# Page06_CPU_IO.net
KiCad netlist of a schematic drawn in Altium Designer
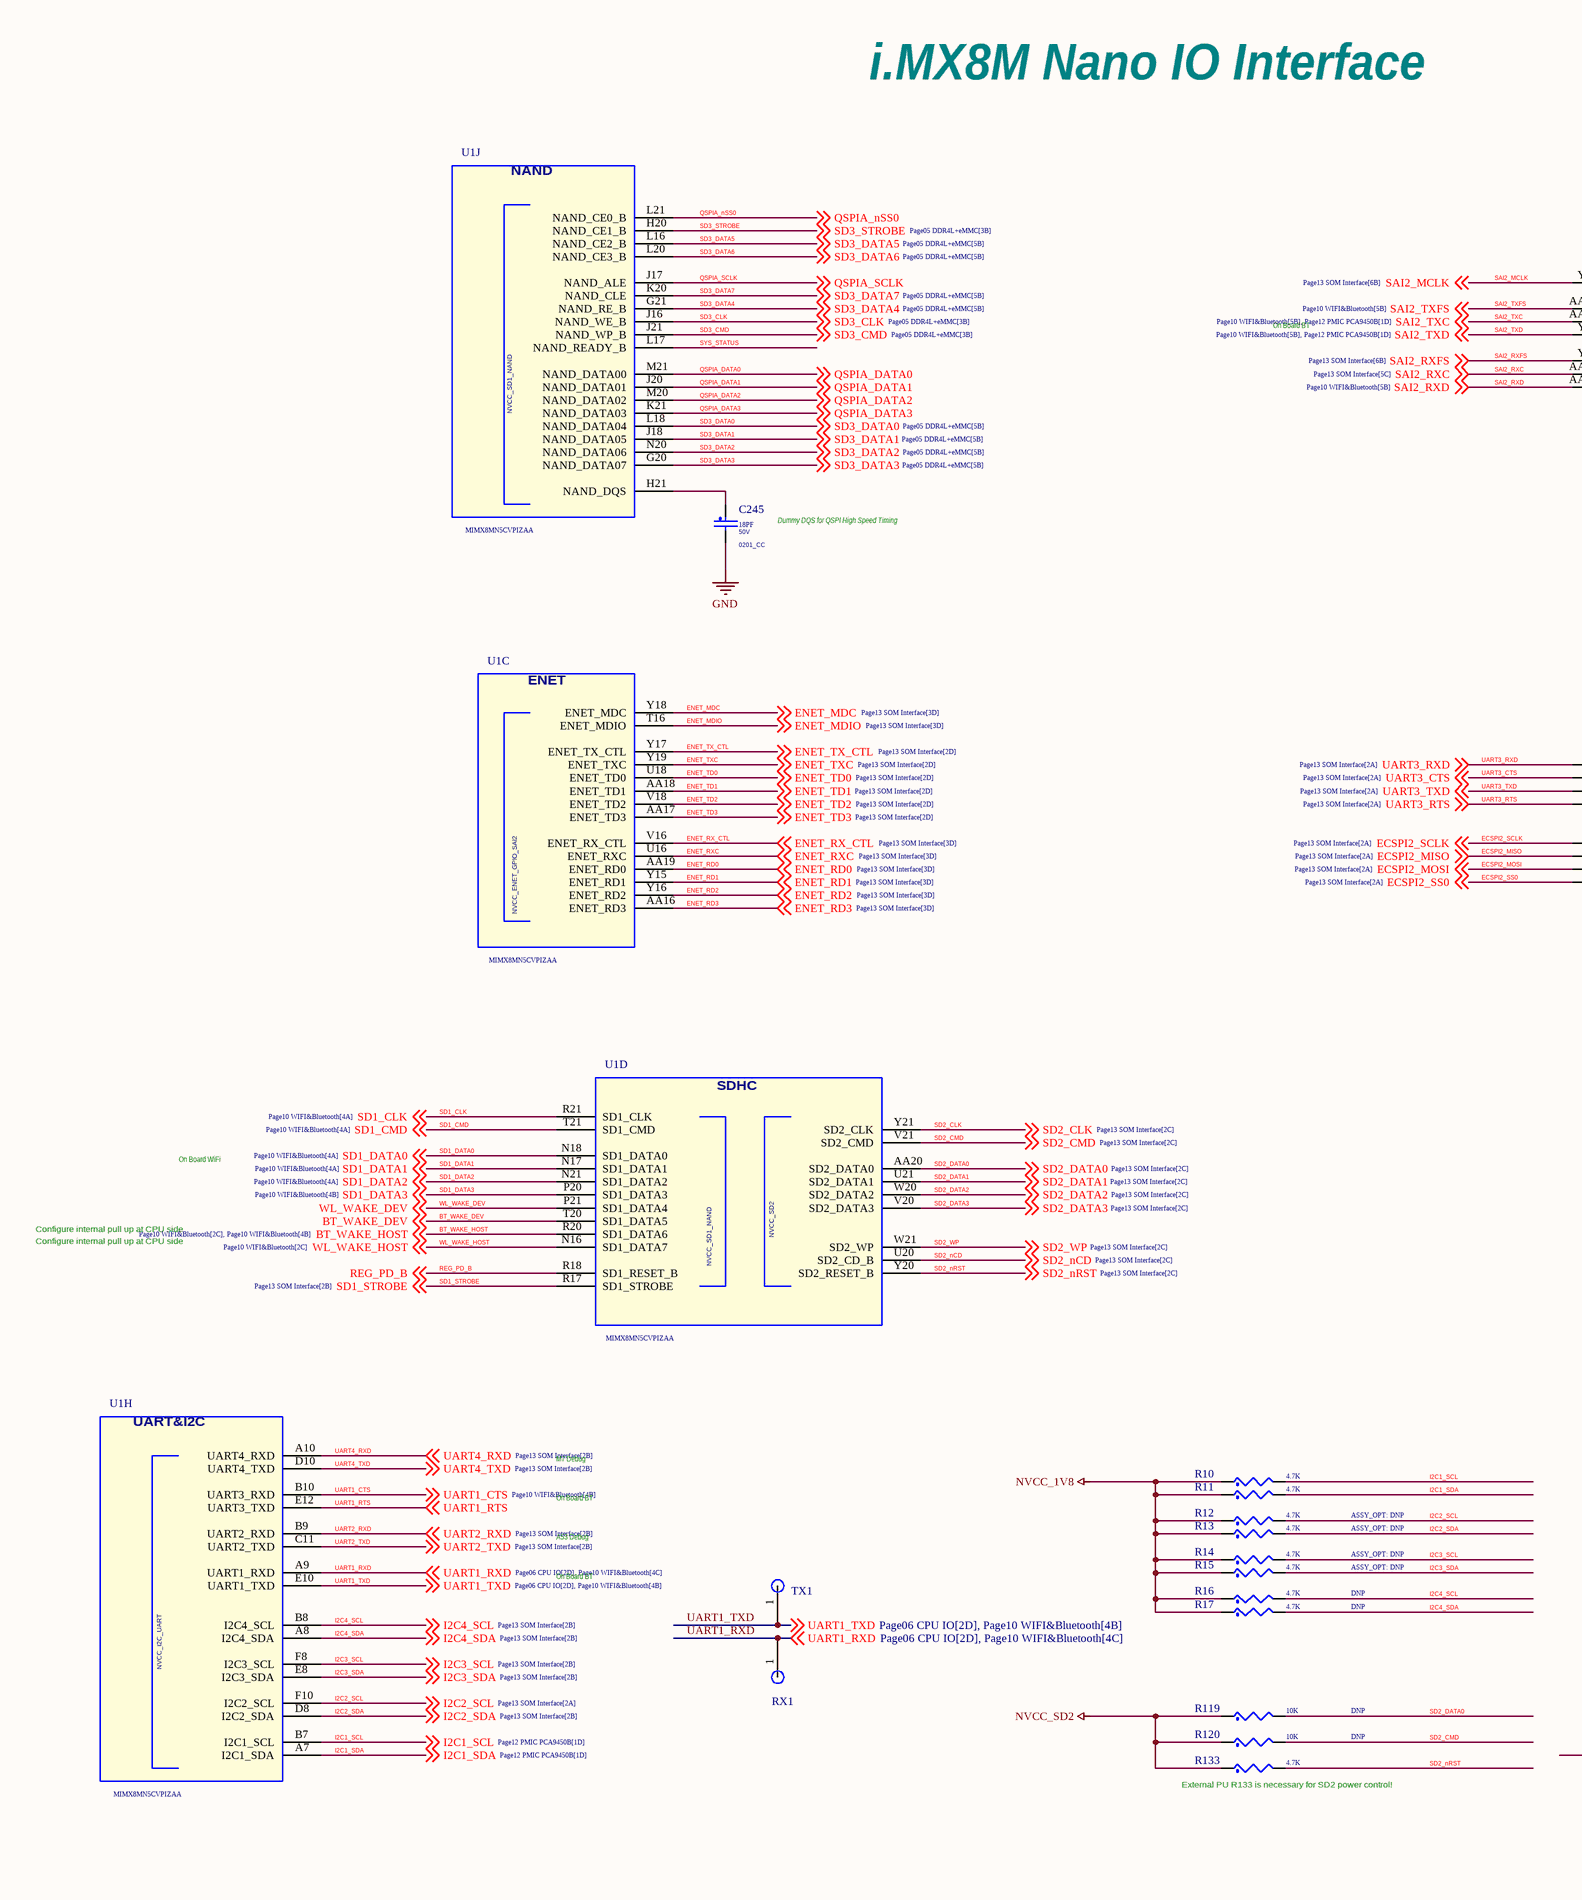
[diagram p0: Page06 CPU IO.SchDoc, left]
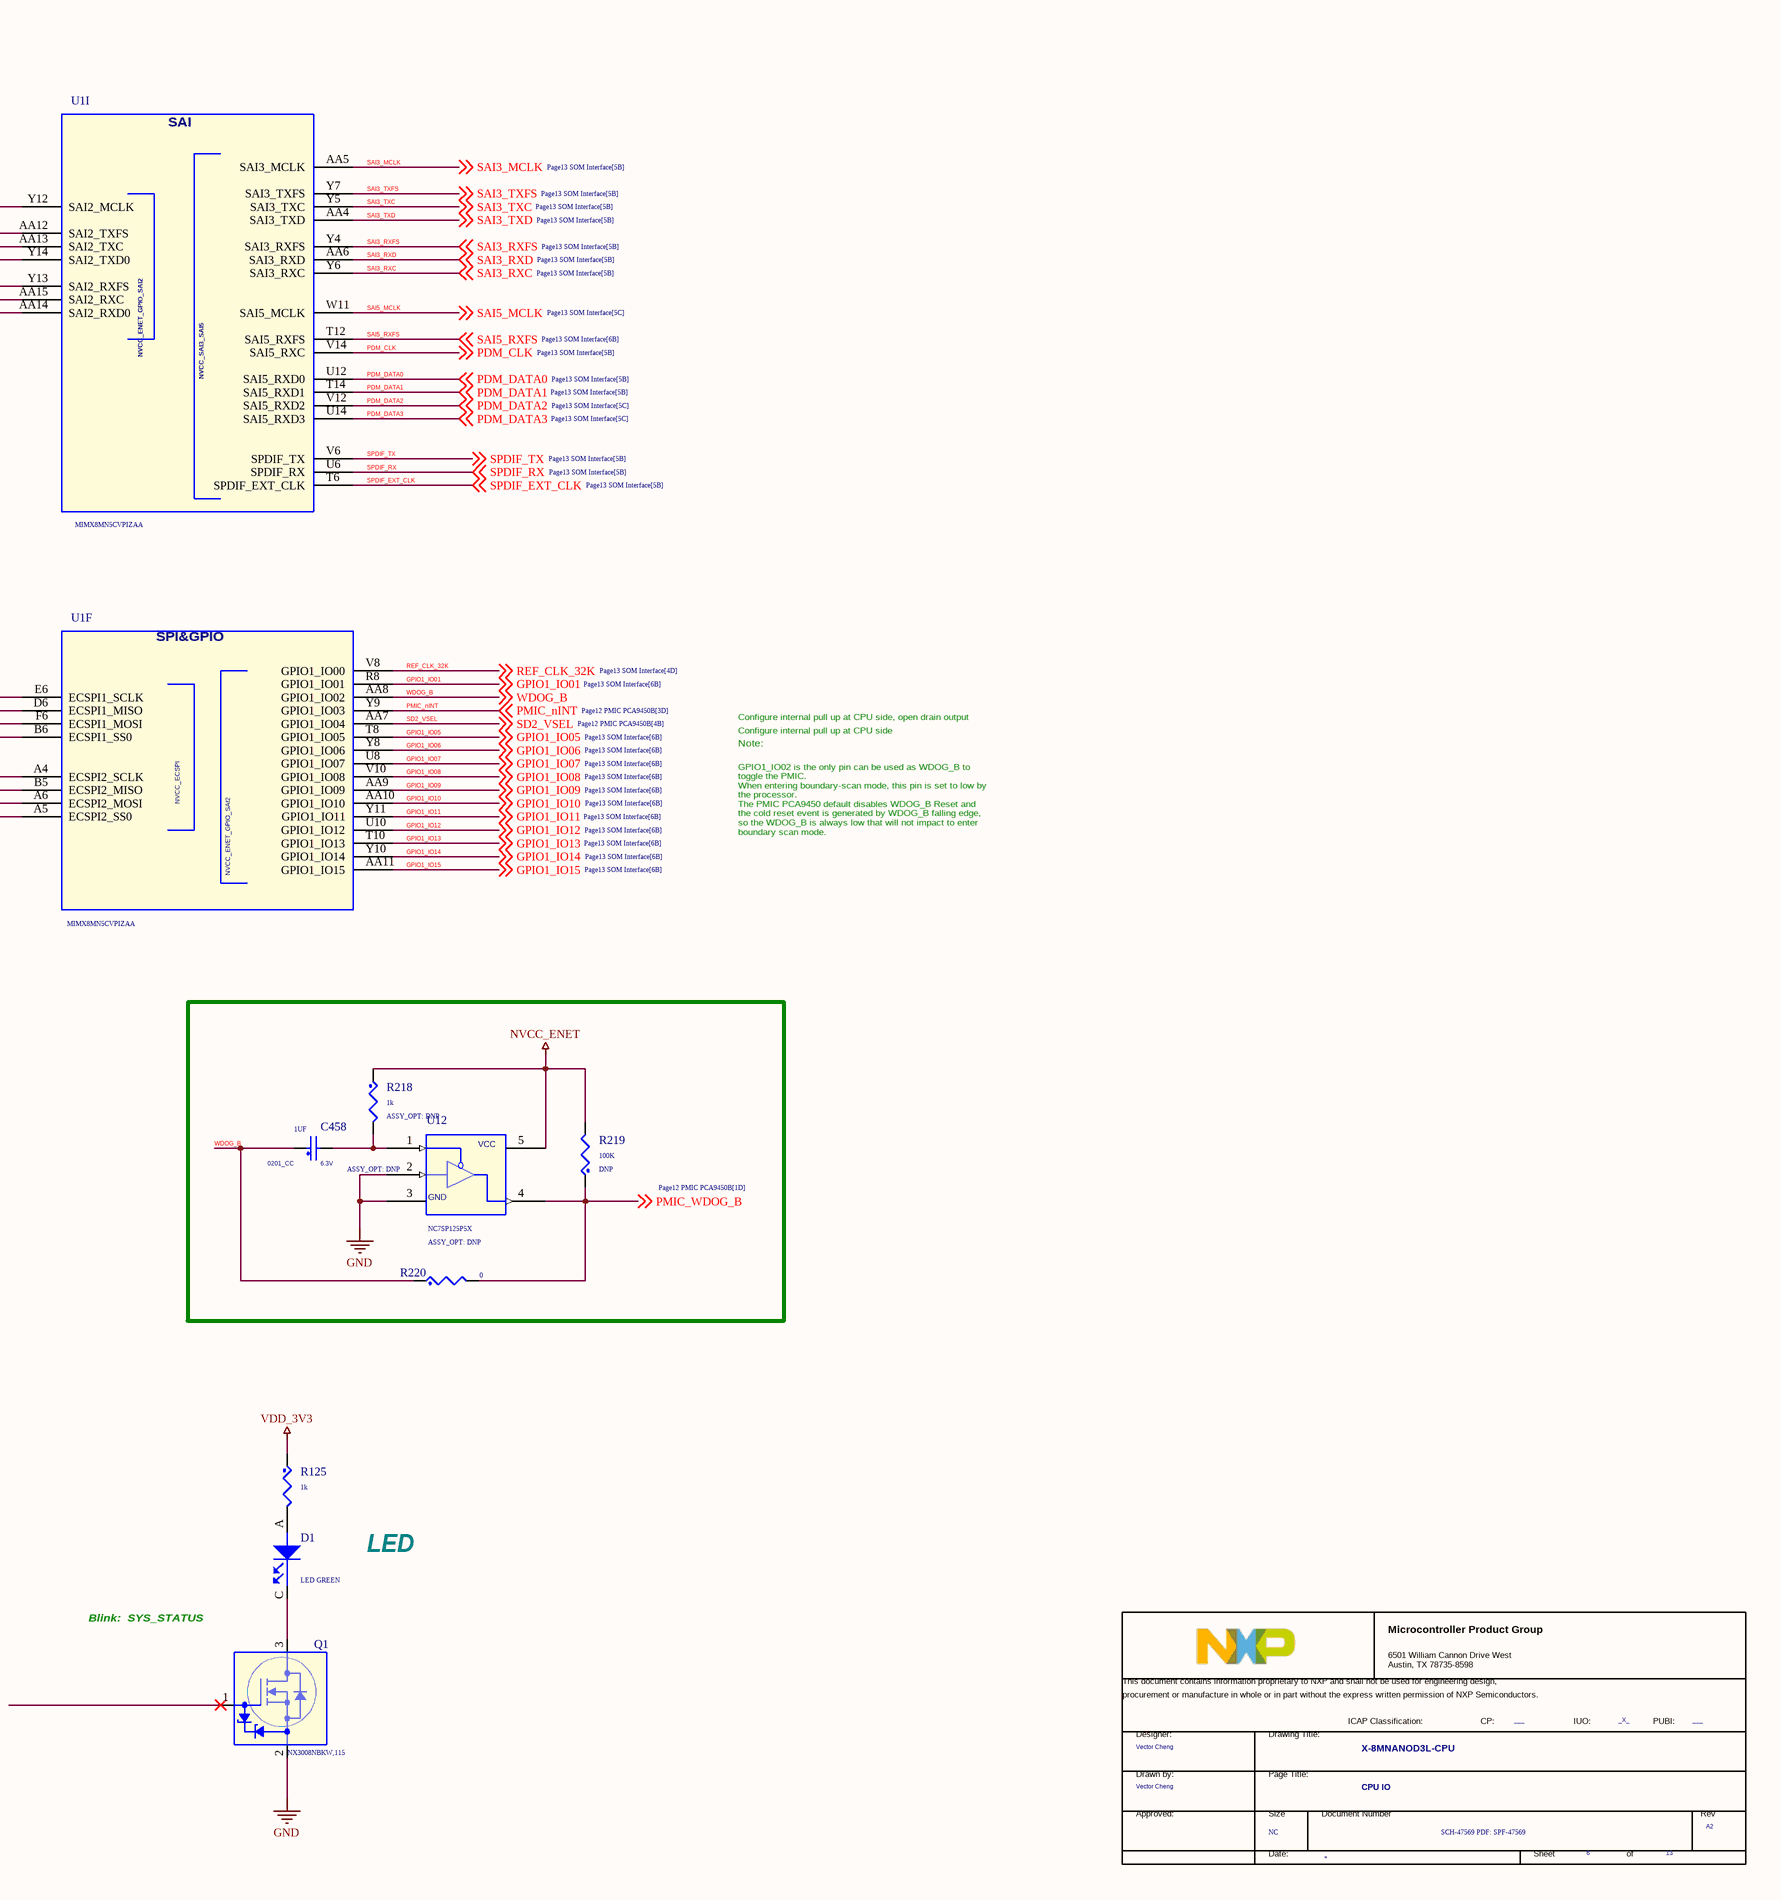
[diagram p1: Page06 CPU IO.SchDoc, right]

(export (version "E")
  (design (tool "Eeschema 10.0.6"))
  (components
    (comp (ref "C245")
      (value "18PF")
      (footprint "0201_CC - C")
      (description "CAP CER 18pF 50V 5% C0G 0201")
      (fields
        (field (name "VOLTAGE") "50V")
        (field (name "TOLERANCE") "5%")
        (field (name "PCB FOOTPRINT") "0201_CC")
      )
      (libsource (lib "*") (part "CAP_NP"))
    )
    (comp (ref "C458")
      (value "1UF")
      (footprint "0201_CC - C")
      (description "CAP CER 1uF 6.3V 20% X5R 0201")
      (fields
        (field (name "ASSY_OPT") "DNP")
        (field (name "PCB FOOTPRINT") "0201_CC")
        (field (name "TOLERANCE") "20%")
        (field (name "VOLTAGE") "6.3V")
      )
      (libsource (lib "*") (part "CAP_NP"))
    )
    (comp (ref "D1")
      (value "LED GREEN")
      (footprint "LED_0603")
      (description "LED GRN SGL 25MA SMT 0603")
      (fields (field (name "VOLTAGE") "2V"))
      (libsource (lib "*") (part "LED"))
    )
    (comp (ref "Q1")
      (value "NX3008NBKW,115")
      (footprint "sc70_3")
      (description "TRAN NMOS SW 30V 350mA AEC-Q101 SC-70")
      (libsource (lib "*") (part "NMOS_NX3008NBK"))
    )
    (comp (ref "R10")
      (value "4.7K")
      (footprint "0201_RES")
      (description "RES MF 4.7K 1/20W 5% AEC-Q200 0201")
      (fields (field (name "TOLERANCE") "5%"))
      (libsource (lib "*") (part "RES"))
    )
    (comp (ref "R11")
      (value "4.7K")
      (footprint "0201_RES")
      (description "RES MF 4.7K 1/20W 5% AEC-Q200 0201")
      (fields (field (name "TOLERANCE") "5%"))
      (libsource (lib "*") (part "RES"))
    )
    (comp (ref "R12")
      (value "4.7K")
      (footprint "0201_RES")
      (description "RES MF 4.7K 1/20W 5% AEC-Q200 0201")
      (fields (field (name "ASSY_OPT") "DNP") (field (name "TOLERANCE") "5%"))
      (libsource (lib "*") (part "RES"))
    )
    (comp (ref "R13")
      (value "4.7K")
      (footprint "0201_RES")
      (description "RES MF 4.7K 1/20W 5% AEC-Q200 0201")
      (fields (field (name "ASSY_OPT") "DNP") (field (name "TOLERANCE") "5%"))
      (libsource (lib "*") (part "RES"))
    )
    (comp (ref "R14")
      (value "4.7K")
      (footprint "0201_RES")
      (description "RES MF 4.7K 1/20W 5% AEC-Q200 0201")
      (fields (field (name "ASSY_OPT") "DNP") (field (name "TOLERANCE") "5%"))
      (libsource (lib "*") (part "RES"))
    )
    (comp (ref "R15")
      (value "4.7K")
      (footprint "0201_RES")
      (description "RES MF 4.7K 1/20W 5% AEC-Q200 0201")
      (fields (field (name "ASSY_OPT") "DNP") (field (name "TOLERANCE") "5%"))
      (libsource (lib "*") (part "RES"))
    )
    (comp (ref "R16")
      (value "4.7K")
      (footprint "0201_RES")
      (description "RES MF 4.7K 1/20W 5% AEC-Q200 0201")
      (fields (field (name "ASSY_OPT") "DNP") (field (name "TOLERANCE") "5%"))
      (libsource (lib "*") (part "RES"))
    )
    (comp (ref "R17")
      (value "4.7K")
      (footprint "0201_RES")
      (description "RES MF 4.7K 1/20W 5% AEC-Q200 0201")
      (fields (field (name "ASSY_OPT") "DNP") (field (name "TOLERANCE") "5%"))
      (libsource (lib "*") (part "RES"))
    )
    (comp (ref "R119")
      (value "10K")
      (footprint "0201_RES")
      (description "RES MF 10K 1/20W 5% 0201")
      (fields (field (name "ASSY_OPT") "DNP") (field (name "TOLERANCE") "5%"))
      (libsource (lib "*") (part "RES"))
    )
    (comp (ref "R120")
      (value "10K")
      (footprint "0201_RES")
      (description "RES MF 10K 1/20W 5% 0201")
      (fields (field (name "ASSY_OPT") "DNP") (field (name "TOLERANCE") "5%"))
      (libsource (lib "*") (part "RES"))
    )
    (comp (ref "R125")
      (value "1k")
      (footprint "0201_RES")
      (description "RES MF 1.0K OHM 1/20W 1% 30V -55+155C 0201")
      (fields (field (name "VOLTAGE") "30") (field (name "TOLERANCE") "1%"))
      (libsource (lib "*") (part "RES"))
    )
    (comp (ref "R133")
      (value "4.7K")
      (footprint "0201_RES")
      (description "RES MF 4.7K 1/20W 5% AEC-Q200 0201")
      (fields (field (name "TOLERANCE") "5%"))
      (libsource (lib "*") (part "RES"))
    )
    (comp (ref "R218")
      (value "1k")
      (footprint "0201_RES")
      (description "RES MF 1.0K OHM 1/20W 1% 30V -55+155C 0201")
      (fields (field (name "ASSY_OPT") "DNP") (field (name "TOLERANCE") "1%") (field (name "VOLTAGE") "30"))
      (libsource (lib "*") (part "RES"))
    )
    (comp (ref "R219")
      (value "100K")
      (footprint "0201_RES")
      (description "RES MF 100K 1/20W 1% 0201")
      (fields (field (name "ASSY_OPT") "DNP") (field (name "TOLERANCE") "1%"))
      (libsource (lib "*") (part "RES"))
    )
    (comp (ref "R220")
      (value "0")
      (footprint "0402_CC")
      (description "RES MF ZERO OHM 1/16W 5% 0402")
      (fields (field (name "TOLERANCE") "5%") (field (name "VOLTAGE") "1/16W"))
      (libsource (lib "*") (part "RES"))
    )
    (comp (ref "RX1")
      (value "Test Pin1")
      (footprint "Test Pin")
      (libsource (lib "Altium starter project NANO") (part "Test Pin1"))
    )
    (comp (ref "TX1")
      (value "Test Pin1")
      (footprint "Test Pin")
      (libsource (lib "Altium starter project NANO") (part "Test Pin1"))
    )
    (comp (ref "U1")
      (value "MIMX8MN5CVPIZAA")
      (footprint "BGA306C50P21X21_1100X1100X101")
      (description "IC CPU QUAD CORTEX A53+M7 1.4GHZ -- BGA306")
      (libsource (lib "*") (part "MIMX8MN"))
    )
    (comp (ref "U12")
      (value "NC7SP125P5X")
      (footprint "SC70-5_A")
      (description "IC BUF TS 0.9-3.6V")
      (fields (field (name "ASSY_OPT") "DNP"))
      (libsource (lib "*") (part "1G125"))
    )
  )
  (nets
    (net (code "1") (name "/SYS_STATUS") (class "Default")
      (node (ref "U1") (pin "L17") (pinfunction "NAND_READY_B_L17") (pintype "passive"))
    )
    (net (code "2") (name "BT_WAKE_DEV") (class "Default")
      (node (ref "U1") (pin "T20") (pinfunction "SD1_DATA5_T20") (pintype "passive"))
    )
    (net (code "3") (name "BT_WAKE_HOST") (class "Default")
      (node (ref "U1") (pin "R20") (pinfunction "SD1_DATA6_R20") (pintype "passive"))
    )
    (net (code "4") (name "ECSPI2_MISO") (class "Default")
      (node (ref "U1") (pin "B5") (pinfunction "ECSPI2_MISO_B5") (pintype "passive"))
    )
    (net (code "5") (name "ECSPI2_MOSI") (class "Default")
      (node (ref "U1") (pin "A6") (pinfunction "ECSPI2_MOSI_A6") (pintype "passive"))
    )
    (net (code "6") (name "ECSPI2_SCLK") (class "Default")
      (node (ref "U1") (pin "A4") (pinfunction "ECSPI2_SCLK_A4") (pintype "passive"))
    )
    (net (code "7") (name "ECSPI2_SS0") (class "Default")
      (node (ref "U1") (pin "A5") (pinfunction "ECSPI2_SS0_A5") (pintype "passive"))
    )
    (net (code "8") (name "ENET_MDC") (class "Default")
      (node (ref "U1") (pin "Y18") (pinfunction "ENET_MDC_Y18") (pintype "passive"))
    )
    (net (code "9") (name "ENET_MDIO") (class "Default")
      (node (ref "U1") (pin "T16") (pinfunction "ENET_MDIO_T16") (pintype "passive"))
    )
    (net (code "10") (name "ENET_RD0") (class "Default")
      (node (ref "U1") (pin "AA19") (pinfunction "ENET_RD0_AA19") (pintype "passive"))
    )
    (net (code "11") (name "ENET_RD1") (class "Default")
      (node (ref "U1") (pin "Y15") (pinfunction "ENET_RD1_Y15") (pintype "passive"))
    )
    (net (code "12") (name "ENET_RD2") (class "Default")
      (node (ref "U1") (pin "Y16") (pinfunction "ENET_RD2_Y16") (pintype "passive"))
    )
    (net (code "13") (name "ENET_RD3") (class "Default")
      (node (ref "U1") (pin "AA16") (pinfunction "ENET_RD3_AA16") (pintype "passive"))
    )
    (net (code "14") (name "ENET_RXC") (class "Default")
      (node (ref "U1") (pin "U16") (pinfunction "ENET_RXC_U16") (pintype "passive"))
    )
    (net (code "15") (name "ENET_RX_CTL") (class "Default")
      (node (ref "U1") (pin "V16") (pinfunction "ENET_RX_CTL_V16") (pintype "passive"))
    )
    (net (code "16") (name "ENET_TD0") (class "Default")
      (node (ref "U1") (pin "U18") (pinfunction "ENET_TD0_U18") (pintype "passive"))
    )
    (net (code "17") (name "ENET_TD1") (class "Default")
      (node (ref "U1") (pin "AA18") (pinfunction "ENET_TD1_AA18") (pintype "passive"))
    )
    (net (code "18") (name "ENET_TD2") (class "Default")
      (node (ref "U1") (pin "V18") (pinfunction "ENET_TD2_V18") (pintype "passive"))
    )
    (net (code "19") (name "ENET_TD3") (class "Default")
      (node (ref "U1") (pin "AA17") (pinfunction "ENET_TD3_AA17") (pintype "passive"))
    )
    (net (code "20") (name "ENET_TXC") (class "Default")
      (node (ref "U1") (pin "Y19") (pinfunction "ENET_TXC_Y19") (pintype "passive"))
    )
    (net (code "21") (name "ENET_TX_CTL") (class "Default")
      (node (ref "U1") (pin "Y17") (pinfunction "ENET_TX_CTL_Y17") (pintype "passive"))
    )
    (net (code "22") (name "GND") (class "Default")
      (node (ref "C245") (pin "2") (pinfunction "2_2") (pintype "passive"))
      (node (ref "Q1") (pin "2") (pinfunction "SOURCE_2") (pintype "passive"))
      (node (ref "U12") (pin "2") (pinfunction "A_2") (pintype "input"))
      (node (ref "U12") (pin "3") (pinfunction "GND_3") (pintype "power_in"))
    )
    (net (code "23") (name "GPIO1_IO01") (class "Default")
      (node (ref "U1") (pin "R8") (pinfunction "GPIO1_IO01_R8") (pintype "passive"))
    )
    (net (code "24") (name "GPIO1_IO05") (class "Default")
      (node (ref "U1") (pin "T8") (pinfunction "GPIO1_IO05_T8") (pintype "passive"))
    )
    (net (code "25") (name "GPIO1_IO06") (class "Default")
      (node (ref "U1") (pin "Y8") (pinfunction "GPIO1_IO06_Y8") (pintype "passive"))
    )
    (net (code "26") (name "GPIO1_IO07") (class "Default")
      (node (ref "U1") (pin "U8") (pinfunction "GPIO1_IO07_U8") (pintype "passive"))
    )
    (net (code "27") (name "GPIO1_IO08") (class "Default")
      (node (ref "U1") (pin "V10") (pinfunction "GPIO1_IO08_V10") (pintype "passive"))
    )
    (net (code "28") (name "GPIO1_IO09") (class "Default")
      (node (ref "U1") (pin "AA9") (pinfunction "GPIO1_IO09_AA9") (pintype "passive"))
    )
    (net (code "29") (name "GPIO1_IO10") (class "Default")
      (node (ref "U1") (pin "AA10") (pinfunction "GPIO1_IO10_AA10") (pintype "passive"))
    )
    (net (code "30") (name "GPIO1_IO11") (class "Default")
      (node (ref "U1") (pin "Y11") (pinfunction "GPIO1_IO11_Y11") (pintype "passive"))
    )
    (net (code "31") (name "GPIO1_IO12") (class "Default")
      (node (ref "U1") (pin "U10") (pinfunction "GPIO1_IO12_U10") (pintype "passive"))
    )
    (net (code "32") (name "GPIO1_IO13") (class "Default")
      (node (ref "U1") (pin "T10") (pinfunction "GPIO1_IO13_T10") (pintype "passive"))
    )
    (net (code "33") (name "GPIO1_IO14") (class "Default")
      (node (ref "U1") (pin "Y10") (pinfunction "GPIO1_IO14_Y10") (pintype "passive"))
    )
    (net (code "34") (name "GPIO1_IO15") (class "Default")
      (node (ref "U1") (pin "AA11") (pinfunction "GPIO1_IO15_AA11") (pintype "passive"))
    )
    (net (code "35") (name "I2C1_SCL") (class "Default")
      (node (ref "R10") (pin "2") (pinfunction "2_2") (pintype "passive"))
      (node (ref "U1") (pin "B7") (pinfunction "I2C1_SCL_B7") (pintype "passive"))
    )
    (net (code "36") (name "I2C1_SDA") (class "Default")
      (node (ref "R11") (pin "2") (pinfunction "2_2") (pintype "passive"))
      (node (ref "U1") (pin "A7") (pinfunction "I2C1_SDA_A7") (pintype "passive"))
    )
    (net (code "37") (name "I2C2_SCL") (class "Default")
      (node (ref "R12") (pin "2") (pinfunction "2_2") (pintype "passive"))
      (node (ref "U1") (pin "F10") (pinfunction "I2C2_SCL_F10") (pintype "passive"))
    )
    (net (code "38") (name "I2C2_SDA") (class "Default")
      (node (ref "R13") (pin "2") (pinfunction "2_2") (pintype "passive"))
      (node (ref "U1") (pin "D8") (pinfunction "I2C2_SDA_D8") (pintype "passive"))
    )
    (net (code "39") (name "I2C3_SCL") (class "Default")
      (node (ref "R14") (pin "2") (pinfunction "2_2") (pintype "passive"))
      (node (ref "U1") (pin "F8") (pinfunction "I2C3_SCL_F8") (pintype "passive"))
    )
    (net (code "40") (name "I2C3_SDA") (class "Default")
      (node (ref "R15") (pin "2") (pinfunction "2_2") (pintype "passive"))
      (node (ref "U1") (pin "E8") (pinfunction "I2C3_SDA_E8") (pintype "passive"))
    )
    (net (code "41") (name "I2C4_SCL") (class "Default")
      (node (ref "R16") (pin "2") (pinfunction "2_2") (pintype "passive"))
      (node (ref "U1") (pin "B8") (pinfunction "I2C4_SCL_B8") (pintype "passive"))
    )
    (net (code "42") (name "I2C4_SDA") (class "Default")
      (node (ref "R17") (pin "2") (pinfunction "2_2") (pintype "passive"))
      (node (ref "U1") (pin "A8") (pinfunction "I2C4_SDA_A8") (pintype "passive"))
    )
    (net (code "43") (name "NVCC_1V8") (class "Default")
      (node (ref "R10") (pin "1") (pinfunction "1_1") (pintype "passive"))
      (node (ref "R11") (pin "1") (pinfunction "1_1") (pintype "passive"))
      (node (ref "R12") (pin "1") (pinfunction "1_1") (pintype "passive"))
      (node (ref "R13") (pin "1") (pinfunction "1_1") (pintype "passive"))
      (node (ref "R14") (pin "1") (pinfunction "1_1") (pintype "passive"))
      (node (ref "R15") (pin "1") (pinfunction "1_1") (pintype "passive"))
      (node (ref "R16") (pin "1") (pinfunction "1_1") (pintype "passive"))
      (node (ref "R17") (pin "1") (pinfunction "1_1") (pintype "passive"))
    )
    (net (code "44") (name "NVCC_ENET") (class "Default")
      (node (ref "R218") (pin "1") (pinfunction "1_1") (pintype "passive"))
      (node (ref "R219") (pin "2") (pinfunction "2_2") (pintype "passive"))
      (node (ref "U12") (pin "5") (pinfunction "VCC_5") (pintype "power_in"))
    )
    (net (code "45") (name "NVCC_SD2") (class "Default")
      (node (ref "R119") (pin "1") (pinfunction "1_1") (pintype "passive"))
      (node (ref "R120") (pin "1") (pinfunction "1_1") (pintype "passive"))
      (node (ref "R133") (pin "1") (pinfunction "1_1") (pintype "passive"))
    )
    (net (code "46") (name "Net-(D1-ANODE)") (class "Default")
      (node (ref "D1") (pin "A") (pinfunction "ANODE_A") (pintype "passive"))
      (node (ref "R125") (pin "2") (pinfunction "2_2") (pintype "passive"))
    )
    (net (code "47") (name "Net-(D1-CATHODE)") (class "Default")
      (node (ref "D1") (pin "C") (pinfunction "CATHODE_C") (pintype "passive"))
      (node (ref "Q1") (pin "3") (pinfunction "DRAIN_3") (pintype "passive"))
    )
    (net (code "48") (name "Net-(U1J-NAND_DQS)") (class "Default")
      (node (ref "C245") (pin "1") (pinfunction "1_1") (pintype "passive"))
      (node (ref "U1") (pin "H21") (pinfunction "NAND_DQS_H21") (pintype "passive"))
    )
    (net (code "49") (name "Net-(U12-~{OE})") (class "Default")
      (node (ref "C458") (pin "2") (pinfunction "2_2") (pintype "passive"))
      (node (ref "R218") (pin "2") (pinfunction "2_2") (pintype "passive"))
      (node (ref "U12") (pin "1") (pinfunction "~{OE}_1") (pintype "input"))
    )
    (net (code "50") (name "PDM_CLK") (class "Default")
      (node (ref "U1") (pin "V14") (pinfunction "SAI5_RXC_V14") (pintype "passive"))
    )
    (net (code "51") (name "PDM_DATA0") (class "Default")
      (node (ref "U1") (pin "U12") (pinfunction "SAI5_RXD0_U12") (pintype "passive"))
    )
    (net (code "52") (name "PDM_DATA1") (class "Default")
      (node (ref "U1") (pin "T14") (pinfunction "SAI5_RXD1_T14") (pintype "passive"))
    )
    (net (code "53") (name "PDM_DATA2") (class "Default")
      (node (ref "U1") (pin "V12") (pinfunction "SAI5_RXD2_V12") (pintype "passive"))
    )
    (net (code "54") (name "PDM_DATA3") (class "Default")
      (node (ref "U1") (pin "U14") (pinfunction "SAI5_RXD3_U14") (pintype "passive"))
    )
    (net (code "55") (name "PMIC_WDOG_B") (class "Default")
      (node (ref "R219") (pin "1") (pinfunction "1_1") (pintype "passive"))
      (node (ref "R220") (pin "2") (pinfunction "2_2") (pintype "passive"))
      (node (ref "U12") (pin "4") (pinfunction "Y_4") (pintype "output"))
    )
    (net (code "56") (name "PMIC_nINT") (class "Default")
      (node (ref "U1") (pin "Y9") (pinfunction "GPIO1_IO03_Y9") (pintype "passive"))
    )
    (net (code "57") (name "QSPIA_DATA0") (class "Default")
      (node (ref "U1") (pin "M21") (pinfunction "NAND_DATA00_M21") (pintype "passive"))
    )
    (net (code "58") (name "QSPIA_DATA1") (class "Default")
      (node (ref "U1") (pin "J20") (pinfunction "NAND_DATA01_J20") (pintype "passive"))
    )
    (net (code "59") (name "QSPIA_DATA2") (class "Default")
      (node (ref "U1") (pin "M20") (pinfunction "NAND_DATA02_M20") (pintype "passive"))
    )
    (net (code "60") (name "QSPIA_DATA3") (class "Default")
      (node (ref "U1") (pin "K21") (pinfunction "NAND_DATA03_K21") (pintype "passive"))
    )
    (net (code "61") (name "QSPIA_SCLK") (class "Default")
      (node (ref "U1") (pin "J17") (pinfunction "NAND_ALE_J17") (pintype "passive"))
    )
    (net (code "62") (name "QSPIA_nSS0") (class "Default")
      (node (ref "U1") (pin "L21") (pinfunction "NAND_CE0_B_L21") (pintype "passive"))
    )
    (net (code "63") (name "REF_CLK_32K") (class "Default")
      (node (ref "U1") (pin "V8") (pinfunction "GPIO1_IO00_V8") (pintype "passive"))
    )
    (net (code "64") (name "REG_PD_B") (class "Default")
      (node (ref "U1") (pin "R18") (pinfunction "SD1_RESET_B_R18") (pintype "passive"))
    )
    (net (code "65") (name "SAI2_MCLK") (class "Default")
      (node (ref "U1") (pin "Y12") (pinfunction "SAI2_MCLK_Y12") (pintype "passive"))
    )
    (net (code "66") (name "SAI2_RXC") (class "Default")
      (node (ref "U1") (pin "AA15") (pinfunction "SAI2_RXC_AA15") (pintype "passive"))
    )
    (net (code "67") (name "SAI2_RXD") (class "Default")
      (node (ref "U1") (pin "AA14") (pinfunction "SAI2_RXD0_AA14") (pintype "passive"))
    )
    (net (code "68") (name "SAI2_RXFS") (class "Default")
      (node (ref "U1") (pin "Y13") (pinfunction "SAI2_RXFS_Y13") (pintype "passive"))
    )
    (net (code "69") (name "SAI2_TXC") (class "Default")
      (node (ref "U1") (pin "AA13") (pinfunction "SAI2_TXC_AA13") (pintype "passive"))
    )
    (net (code "70") (name "SAI2_TXD") (class "Default")
      (node (ref "U1") (pin "Y14") (pinfunction "SAI2_TXD0_Y14") (pintype "passive"))
    )
    (net (code "71") (name "SAI2_TXFS") (class "Default")
      (node (ref "U1") (pin "AA12") (pinfunction "SAI2_TXFS_AA12") (pintype "passive"))
    )
    (net (code "72") (name "SAI3_MCLK") (class "Default")
      (node (ref "U1") (pin "AA5") (pinfunction "SAI3_MCLK_AA5") (pintype "passive"))
    )
    (net (code "73") (name "SAI3_RXC") (class "Default")
      (node (ref "U1") (pin "Y6") (pinfunction "SAI3_RXC_Y6") (pintype "passive"))
    )
    (net (code "74") (name "SAI3_RXD") (class "Default")
      (node (ref "U1") (pin "AA6") (pinfunction "SAI3_RXD_AA6") (pintype "passive"))
    )
    (net (code "75") (name "SAI3_RXFS") (class "Default")
      (node (ref "U1") (pin "Y4") (pinfunction "SAI3_RXFS_Y4") (pintype "passive"))
    )
    (net (code "76") (name "SAI3_TXC") (class "Default")
      (node (ref "U1") (pin "Y5") (pinfunction "SAI3_TXC_Y5") (pintype "passive"))
    )
    (net (code "77") (name "SAI3_TXD") (class "Default")
      (node (ref "U1") (pin "AA4") (pinfunction "SAI3_TXD_AA4") (pintype "passive"))
    )
    (net (code "78") (name "SAI3_TXFS") (class "Default")
      (node (ref "U1") (pin "Y7") (pinfunction "SAI3_TXFS_Y7") (pintype "passive"))
    )
    (net (code "79") (name "SAI5_MCLK") (class "Default")
      (node (ref "U1") (pin "W11") (pinfunction "SAI5_MCLK_W11") (pintype "passive"))
    )
    (net (code "80") (name "SAI5_RXFS") (class "Default")
      (node (ref "U1") (pin "T12") (pinfunction "SAI5_RXFS_T12") (pintype "passive"))
    )
    (net (code "81") (name "SD1_CLK") (class "Default")
      (node (ref "U1") (pin "R21") (pinfunction "SD1_CLK_R21") (pintype "passive"))
    )
    (net (code "82") (name "SD1_CMD") (class "Default")
      (node (ref "U1") (pin "T21") (pinfunction "SD1_CMD_T21") (pintype "passive"))
    )
    (net (code "83") (name "SD1_DATA0") (class "Default")
      (node (ref "U1") (pin "N18") (pinfunction "SD1_DATA0_N18") (pintype "passive"))
    )
    (net (code "84") (name "SD1_DATA1") (class "Default")
      (node (ref "U1") (pin "N17") (pinfunction "SD1_DATA1_N17") (pintype "passive"))
    )
    (net (code "85") (name "SD1_DATA2") (class "Default")
      (node (ref "U1") (pin "N21") (pinfunction "SD1_DATA2_N21") (pintype "passive"))
    )
    (net (code "86") (name "SD1_DATA3") (class "Default")
      (node (ref "U1") (pin "P20") (pinfunction "SD1_DATA3_P20") (pintype "passive"))
    )
    (net (code "87") (name "SD1_STROBE") (class "Default")
      (node (ref "U1") (pin "R17") (pinfunction "SD1_STROBE_R17") (pintype "passive"))
    )
    (net (code "88") (name "SD2_CLK") (class "Default")
      (node (ref "U1") (pin "Y21") (pinfunction "SD2_CLK_Y21") (pintype "passive"))
    )
    (net (code "89") (name "SD2_CMD") (class "Default")
      (node (ref "R120") (pin "2") (pinfunction "2_2") (pintype "passive"))
      (node (ref "U1") (pin "V21") (pinfunction "SD2_CMD_V21") (pintype "passive"))
    )
    (net (code "90") (name "SD2_DATA0") (class "Default")
      (node (ref "R119") (pin "2") (pinfunction "2_2") (pintype "passive"))
      (node (ref "U1") (pin "AA20") (pinfunction "SD2_DATA0_AA20") (pintype "passive"))
    )
    (net (code "91") (name "SD2_DATA1") (class "Default")
      (node (ref "U1") (pin "U21") (pinfunction "SD2_DATA1_U21") (pintype "passive"))
    )
    (net (code "92") (name "SD2_DATA2") (class "Default")
      (node (ref "U1") (pin "W20") (pinfunction "SD2_DATA2_W20") (pintype "passive"))
    )
    (net (code "93") (name "SD2_DATA3") (class "Default")
      (node (ref "U1") (pin "V20") (pinfunction "SD2_DATA3_V20") (pintype "passive"))
    )
    (net (code "94") (name "SD2_VSEL") (class "Default")
      (node (ref "U1") (pin "AA7") (pinfunction "GPIO1_IO04_AA7") (pintype "passive"))
    )
    (net (code "95") (name "SD2_WP") (class "Default")
      (node (ref "U1") (pin "W21") (pinfunction "SD2_WP_W21") (pintype "passive"))
    )
    (net (code "96") (name "SD2_nCD") (class "Default")
      (node (ref "U1") (pin "U20") (pinfunction "SD2_CD_B_U20") (pintype "passive"))
    )
    (net (code "97") (name "SD2_nRST") (class "Default")
      (node (ref "R133") (pin "2") (pinfunction "2_2") (pintype "passive"))
      (node (ref "U1") (pin "Y20") (pinfunction "SD2_RESET_B_Y20") (pintype "passive"))
    )
    (net (code "98") (name "SD3_CLK") (class "Default")
      (node (ref "U1") (pin "J16") (pinfunction "NAND_WE_B_J16") (pintype "passive"))
    )
    (net (code "99") (name "SD3_CMD") (class "Default")
      (node (ref "U1") (pin "J21") (pinfunction "NAND_WP_B_J21") (pintype "passive"))
    )
    (net (code "100") (name "SD3_DATA0") (class "Default")
      (node (ref "U1") (pin "L18") (pinfunction "NAND_DATA04_L18") (pintype "passive"))
    )
    (net (code "101") (name "SD3_DATA1") (class "Default")
      (node (ref "U1") (pin "J18") (pinfunction "NAND_DATA05_J18") (pintype "passive"))
    )
    (net (code "102") (name "SD3_DATA2") (class "Default")
      (node (ref "U1") (pin "N20") (pinfunction "NAND_DATA06_N20") (pintype "passive"))
    )
    (net (code "103") (name "SD3_DATA3") (class "Default")
      (node (ref "U1") (pin "G20") (pinfunction "NAND_DATA07_G20") (pintype "passive"))
    )
    (net (code "104") (name "SD3_DATA4") (class "Default")
      (node (ref "U1") (pin "G21") (pinfunction "NAND_RE_B_G21") (pintype "passive"))
    )
    (net (code "105") (name "SD3_DATA5") (class "Default")
      (node (ref "U1") (pin "L16") (pinfunction "NAND_CE2_B_L16") (pintype "passive"))
    )
    (net (code "106") (name "SD3_DATA6") (class "Default")
      (node (ref "U1") (pin "L20") (pinfunction "NAND_CE3_B_L20") (pintype "passive"))
    )
    (net (code "107") (name "SD3_DATA7") (class "Default")
      (node (ref "U1") (pin "K20") (pinfunction "NAND_CLE_K20") (pintype "passive"))
    )
    (net (code "108") (name "SD3_STROBE") (class "Default")
      (node (ref "U1") (pin "H20") (pinfunction "NAND_CE1_B_H20") (pintype "passive"))
    )
    (net (code "109") (name "SPDIF_EXT_CLK") (class "Default")
      (node (ref "U1") (pin "T6") (pinfunction "SPDIF_EXT_CLK_T6") (pintype "passive"))
    )
    (net (code "110") (name "SPDIF_RX") (class "Default")
      (node (ref "U1") (pin "U6") (pinfunction "SPDIF_RX_U6") (pintype "passive"))
    )
    (net (code "111") (name "SPDIF_TX") (class "Default")
      (node (ref "U1") (pin "V6") (pinfunction "SPDIF_TX_V6") (pintype "passive"))
    )
    (net (code "112") (name "UART1_CTS") (class "Default")
      (node (ref "U1") (pin "B10") (pinfunction "UART3_RXD_B10") (pintype "passive"))
    )
    (net (code "113") (name "UART1_RTS") (class "Default")
      (node (ref "U1") (pin "E12") (pinfunction "UART3_TXD_E12") (pintype "passive"))
    )
    (net (code "114") (name "UART1_RXD") (class "Default")
      (node (ref "RX1") (pin "1") (pinfunction "1_1") (pintype "passive"))
      (node (ref "U1") (pin "A9") (pinfunction "UART1_RXD_A9") (pintype "passive"))
    )
    (net (code "115") (name "UART1_TXD") (class "Default")
      (node (ref "TX1") (pin "1") (pinfunction "1_1") (pintype "passive"))
      (node (ref "U1") (pin "E10") (pinfunction "UART1_TXD_E10") (pintype "passive"))
    )
    (net (code "116") (name "UART2_RXD") (class "Default")
      (node (ref "U1") (pin "B9") (pinfunction "UART2_RXD_B9") (pintype "passive"))
    )
    (net (code "117") (name "UART2_TXD") (class "Default")
      (node (ref "U1") (pin "C11") (pinfunction "UART2_TXD_C11") (pintype "passive"))
    )
    (net (code "118") (name "UART3_CTS") (class "Default")
      (node (ref "U1") (pin "D6") (pinfunction "ECSPI1_MISO_D6") (pintype "passive"))
    )
    (net (code "119") (name "UART3_RTS") (class "Default")
      (node (ref "U1") (pin "B6") (pinfunction "ECSPI1_SS0_B6") (pintype "passive"))
    )
    (net (code "120") (name "UART3_RXD") (class "Default")
      (node (ref "U1") (pin "E6") (pinfunction "ECSPI1_SCLK_E6") (pintype "passive"))
    )
    (net (code "121") (name "UART3_TXD") (class "Default")
      (node (ref "U1") (pin "F6") (pinfunction "ECSPI1_MOSI_F6") (pintype "passive"))
    )
    (net (code "122") (name "UART4_RXD") (class "Default")
      (node (ref "U1") (pin "A10") (pinfunction "UART4_RXD_A10") (pintype "passive"))
    )
    (net (code "123") (name "UART4_TXD") (class "Default")
      (node (ref "U1") (pin "D10") (pinfunction "UART4_TXD_D10") (pintype "passive"))
    )
    (net (code "124") (name "VDD_3V3") (class "Default")
      (node (ref "R125") (pin "1") (pinfunction "1_1") (pintype "passive"))
    )
    (net (code "125") (name "WDOG_B") (class "Default")
      (node (ref "C458") (pin "1") (pinfunction "1_1") (pintype "passive"))
      (node (ref "R220") (pin "1") (pinfunction "1_1") (pintype "passive"))
      (node (ref "U1") (pin "AA8") (pinfunction "GPIO1_IO02_AA8") (pintype "passive"))
    )
    (net (code "126") (name "WL_WAKE_DEV") (class "Default")
      (node (ref "U1") (pin "P21") (pinfunction "SD1_DATA4_P21") (pintype "passive"))
    )
    (net (code "127") (name "WL_WAKE_HOST") (class "Default")
      (node (ref "U1") (pin "N16") (pinfunction "SD1_DATA7_N16") (pintype "passive"))
    )
    (net (code "128") (name "unconnected-(Q1-GATE-Pad1)") (class "Default")
      (node (ref "Q1") (pin "1") (pinfunction "GATE_1") (pintype "passive+no_connect"))
    )
  )
)
